# STM32_microcontroller_IOs.net
KiCad netlist of a schematic drawn in Altium Designer
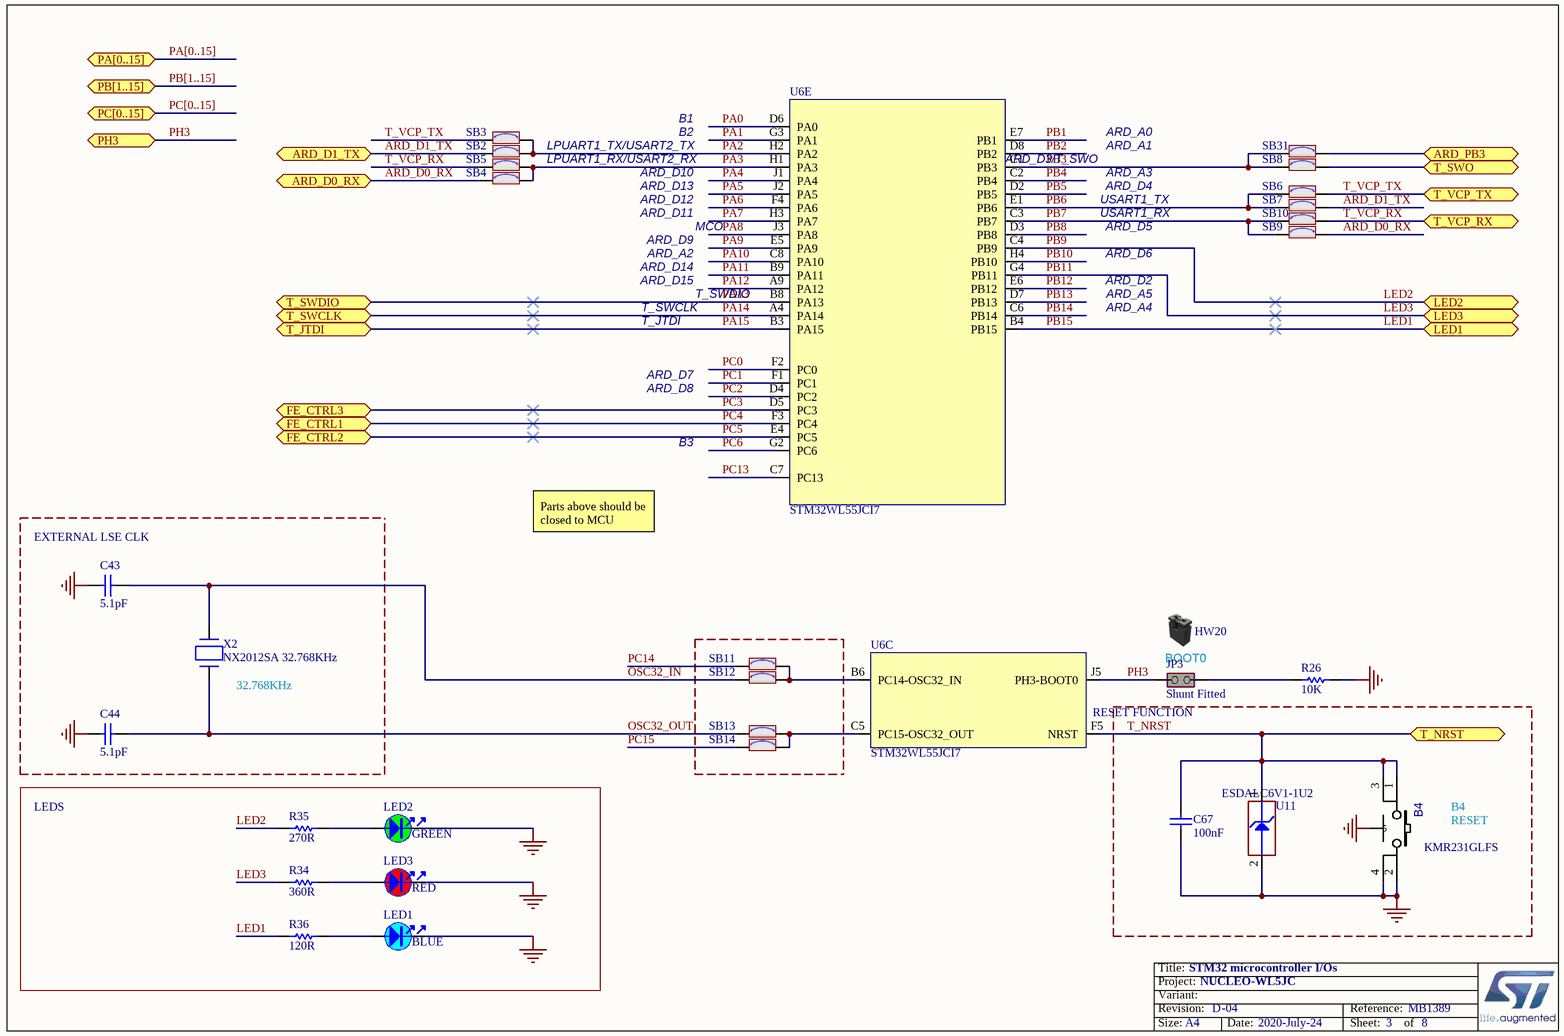
[diagram p0: STM32_microcontroller_IOs.SchDoc]

(export (version "E")
  (design (tool "Eeschema 10.0.6"))
  (components
    (comp (ref "B4")
      (value "KMR231GLFS")
      (footprint "SWI_C&K_Y78B23110FP__ITT_KMR231GLFS")
      (description "Microminiature Tact Switch for SMT - KMR 2 Series - 1.9 mm height")
      (fields
        (field (name "INTERNAL_PART_NUMBER") "MCD-01485")
        (field (name "MANUFACTURER") "C&K")
        (field (name "PROVIDED_BY") "SUBCO")
      )
      (libsource (lib "MCD_PARTS_database") (part "SW-PUSH-CMS_KMR2_BLACK"))
    )
    (comp (ref "C43")
      (value "5.1pF")
      (footprint "C0402")
      (description "Capacitor, MLCC, 5.1pF, 50V, NPO, +-0.25pF, 0402, T=0.5mm")
      (fields
        (field (name "INTERNAL_PART_NUMBER") "MCD-00003")
        (field (name "MANUFACTURER_PART_NUMBER") "CC0402CRNPO9BN5R1")
        (field (name "PROVIDED_BY") "SUBCO")
      )
      (libsource (lib "MCD_PARTS_database") (part "Capacitor"))
    )
    (comp (ref "C44")
      (value "5.1pF")
      (footprint "C0402")
      (description "Capacitor, MLCC, 5.1pF, 50V, NPO, +-0.25pF, 0402, T=0.5mm")
      (fields
        (field (name "INTERNAL_PART_NUMBER") "MCD-00003")
        (field (name "MANUFACTURER_PART_NUMBER") "CC0402CRNPO9BN5R1")
        (field (name "PROVIDED_BY") "SUBCO")
      )
      (libsource (lib "MCD_PARTS_database") (part "Capacitor"))
    )
    (comp (ref "C67")
      (value "100nF")
      (footprint "C0402")
      (description "Capacitor, MLCC, 100nF, 16V, X7R, 10%, 0402, T=0,5mm")
      (fields
        (field (name "INTERNAL_PART_NUMBER") "MCD-00102")
        (field (name "MANUFACTURER_PART_NUMBER") "CC0402KRX7R7BB104")
        (field (name "PROVIDED_BY") "SUBCO")
      )
      (libsource (lib "MCD_PARTS_database") (part "Capacitor"))
    )
    (comp (ref "HW20")
      (value "~")
      (description "SHUNT 2.54mm BLACK")
      (fields
        (field (name "INTERNAL_PART_NUMBER") "MCD-00043")
        (field (name "MANUFACTURER_PART_NUMBER") "SNT-100-BK-G")
        (field (name "PROVIDED_BY") "SUBCO")
      )
      (libsource (lib "MCD_PARTS_database") (part "Shunt Black 2.54mm"))
    )
    (comp (ref "JP3")
      (value "Shunt Fitted")
      (footprint "CON_SAMTEC_TSW-102-07-G-S")
      (description "Header, 2x1, 2,54mm, VR, TH, Height 5.84mm/2.54mm - Shunt Fitted by default")
      (fields
        (field (name "INTERNAL_PART_NUMBER") "MCD-00683")
        (field (name "MANUFACTURER_PART_NUMBER") "TSW-102-07-x-S")
        (field (name "PROVIDED_BY") "SUBCO")
      )
      (libsource (lib "MCD_PARTS_database") (part "Jumper_Header 2x1 Fitted"))
    )
    (comp (ref "LED1")
      (value "BLUE")
      (footprint "LED_0603_OSRAM_LB-Q39G-L2OO-35-1_BLUE_1A2K_H0P4")
      (description "LED Blue, 0603 SMD, Forward Voltage Min=2,8V, Max=3,8V")
      (fields
        (field (name "INTERNAL_PART_NUMBER") "MCD-00585")
        (field (name "MANUFACTURER_PART_NUMBER") "LB Q39G-L2OO-35-1")
        (field (name "PROVIDED_BY") "SUBCO")
      )
      (libsource (lib "MCD_PARTS_database") (part "LED_blue"))
    )
    (comp (ref "LED2")
      (value "GREEN")
      (footprint "LED_0603_OSRAM_LG-Q396-PS-35_GREEN_1A2K_H0P4")
      (description "LED Green, 0603 SMD, Forward Voltage Typ=2V, Max=2.5V")
      (fields
        (field (name "INTERNAL_PART_NUMBER") "MCD-00588")
        (field (name "MANUFACTURER_PART_NUMBER") "LG Q396-PS-35")
        (field (name "PROVIDED_BY") "SUBCO")
      )
      (libsource (lib "MCD_PARTS_database") (part "LED_green"))
    )
    (comp (ref "LED3")
      (value "RED")
      (footprint "LED_0603_VISHAY_VLMS1300-GS08_RED_1A2K_H0P8")
      (description "LED Red, 0603 SMD, 2V Forward Voltage")
      (fields
        (field (name "INTERNAL_PART_NUMBER") "MCD-00587")
        (field (name "MANUFACTURER_PART_NUMBER") "VLMS1300-GS08")
        (field (name "PROVIDED_BY") "SUBCO")
      )
      (libsource (lib "MCD_PARTS_database") (part "LED_red"))
    )
    (comp (ref "R26")
      (value "10K")
      (footprint "R0603")
      (description "Resistor,10K,0603,1%,1/10W")
      (fields
        (field (name "INTERNAL_PART_NUMBER") "MCD-00220")
        (field (name "MANUFACTURER_PART_NUMBER") "RC0603FR-0710KL")
        (field (name "PROVIDED_BY") "SUBCO")
      )
      (libsource (lib "MCD_PARTS_database") (part "Resistor"))
    )
    (comp (ref "R34")
      (value "360R")
      (footprint "R0402")
      (description "Resistor,360R,0402,1%,1/16W")
      (fields
        (field (name "INTERNAL_PART_NUMBER") "MCD-00461")
        (field (name "MANUFACTURER_PART_NUMBER") "RC0402FR-07360RL")
        (field (name "PROVIDED_BY") "SUBCO")
      )
      (libsource (lib "MCD_PARTS_database") (part "Resistor"))
    )
    (comp (ref "R35")
      (value "270R")
      (footprint "R0402")
      (description "Resistor,270R,0402,1%,1/16W")
      (fields
        (field (name "INTERNAL_PART_NUMBER") "MCD-00441")
        (field (name "MANUFACTURER_PART_NUMBER") "RC0402FR-07270RL")
        (field (name "PROVIDED_BY") "SUBCO")
      )
      (libsource (lib "MCD_PARTS_database") (part "Resistor"))
    )
    (comp (ref "R36")
      (value "120R")
      (footprint "R0402")
      (description "Resistor,120R,0402,1%,1/16W")
      (fields
        (field (name "INTERNAL_PART_NUMBER") "MCD-00194")
        (field (name "MANUFACTURER_PART_NUMBER") "RC0402FR-07120RL")
        (field (name "PROVIDED_BY") "SUBCO")
      )
      (libsource (lib "MCD_PARTS_database") (part "Resistor"))
    )
    (comp (ref "SB2")
      (value "~")
      (footprint "SOLDER-BRIDGE_R0603-0R")
      (description "Solder Bridge ON")
      (fields
        (field (name "INTERNAL_PART_NUMBER") "MCD-00071")
        (field (name "MANUFACTURER_PART_NUMBER") "RC0603JR-070RL")
        (field (name "PROVIDED_BY") "SUBCO")
      )
      (libsource (lib "") (part "SB_ON_1"))
    )
    (comp (ref "SB3")
      (value "~")
      (footprint "SOLDER-BRIDGE_R0603-0R")
      (description "Solder Bridge ON")
      (fields
        (field (name "INTERNAL_PART_NUMBER") "MCD-00071")
        (field (name "MANUFACTURER_PART_NUMBER") "RC0603JR-070RL")
        (field (name "PROVIDED_BY") "SUBCO")
      )
      (libsource (lib "MCD_PARTS_database") (part "SB_ON"))
    )
    (comp (ref "SB4")
      (value "~")
      (footprint "SOLDER-BRIDGE_R0603-0R")
      (description "Solder Bridge ON")
      (fields
        (field (name "INTERNAL_PART_NUMBER") "MCD-00071")
        (field (name "MANUFACTURER_PART_NUMBER") "RC0603JR-070RL")
        (field (name "PROVIDED_BY") "SUBCO")
      )
      (libsource (lib "") (part "SB_ON_1"))
    )
    (comp (ref "SB5")
      (value "~")
      (footprint "SOLDER-BRIDGE_R0603-0R")
      (description "Solder Bridge ON")
      (fields
        (field (name "INTERNAL_PART_NUMBER") "MCD-00071")
        (field (name "MANUFACTURER_PART_NUMBER") "RC0603JR-070RL")
        (field (name "PROVIDED_BY") "SUBCO")
      )
      (libsource (lib "MCD_PARTS_database") (part "SB_ON"))
    )
    (comp (ref "SB6")
      (value "~")
      (footprint "SOLDER-BRIDGE_R0603-0R")
      (description "Solder Bridge ON")
      (fields
        (field (name "INTERNAL_PART_NUMBER") "MCD-00071")
        (field (name "MANUFACTURER_PART_NUMBER") "RC0603JR-070RL")
        (field (name "PROVIDED_BY") "SUBCO")
      )
      (libsource (lib "MCD_PARTS_database") (part "SB_ON"))
    )
    (comp (ref "SB7")
      (value "~")
      (footprint "SOLDER-BRIDGE_R0603-0R")
      (description "Solder Bridge ON")
      (fields
        (field (name "INTERNAL_PART_NUMBER") "MCD-00071")
        (field (name "MANUFACTURER_PART_NUMBER") "RC0603JR-070RL")
        (field (name "PROVIDED_BY") "SUBCO")
      )
      (libsource (lib "") (part "SB_ON_1"))
    )
    (comp (ref "SB8")
      (value "~")
      (footprint "SOLDER-BRIDGE_R0603-0R")
      (description "Solder Bridge ON")
      (fields
        (field (name "INTERNAL_PART_NUMBER") "MCD-00071")
        (field (name "MANUFACTURER_PART_NUMBER") "RC0603JR-070RL")
        (field (name "PROVIDED_BY") "SUBCO")
      )
      (libsource (lib "MCD_PARTS_database") (part "SB_ON"))
    )
    (comp (ref "SB9")
      (value "~")
      (footprint "SOLDER-BRIDGE_R0603-0R")
      (description "Solder Bridge ON")
      (fields
        (field (name "INTERNAL_PART_NUMBER") "MCD-00071")
        (field (name "MANUFACTURER_PART_NUMBER") "RC0603JR-070RL")
        (field (name "PROVIDED_BY") "SUBCO")
      )
      (libsource (lib "") (part "SB_ON_1"))
    )
    (comp (ref "SB10")
      (value "~")
      (footprint "SOLDER-BRIDGE_R0603-0R")
      (description "Solder Bridge ON")
      (fields
        (field (name "INTERNAL_PART_NUMBER") "MCD-00071")
        (field (name "MANUFACTURER_PART_NUMBER") "RC0603JR-070RL")
        (field (name "PROVIDED_BY") "SUBCO")
      )
      (libsource (lib "MCD_PARTS_database") (part "SB_ON"))
    )
    (comp (ref "SB11")
      (value "~")
      (footprint "SOLDER-BRIDGE_R0603-0R")
      (description "Solder Bridge ON")
      (fields
        (field (name "INTERNAL_PART_NUMBER") "MCD-00071")
        (field (name "MANUFACTURER_PART_NUMBER") "RC0603JR-070RL")
        (field (name "PROVIDED_BY") "SUBCO")
      )
      (libsource (lib "MCD_PARTS_database") (part "SB_ON"))
    )
    (comp (ref "SB12")
      (value "~")
      (footprint "SOLDER-BRIDGE_R0603-0R")
      (description "Solder Bridge ON")
      (fields
        (field (name "INTERNAL_PART_NUMBER") "MCD-00071")
        (field (name "MANUFACTURER_PART_NUMBER") "RC0603JR-070RL")
        (field (name "PROVIDED_BY") "SUBCO")
      )
      (libsource (lib "MCD_PARTS_database") (part "SB_ON"))
    )
    (comp (ref "SB13")
      (value "~")
      (footprint "SOLDER-BRIDGE_R0603-0R")
      (description "Solder Bridge ON")
      (fields
        (field (name "INTERNAL_PART_NUMBER") "MCD-00071")
        (field (name "MANUFACTURER_PART_NUMBER") "RC0603JR-070RL")
        (field (name "PROVIDED_BY") "SUBCO")
      )
      (libsource (lib "MCD_PARTS_database") (part "SB_ON"))
    )
    (comp (ref "SB14")
      (value "~")
      (footprint "SOLDER-BRIDGE_R0603-0R")
      (description "Solder Bridge ON")
      (fields
        (field (name "INTERNAL_PART_NUMBER") "MCD-00071")
        (field (name "MANUFACTURER_PART_NUMBER") "RC0603JR-070RL")
        (field (name "PROVIDED_BY") "SUBCO")
      )
      (libsource (lib "MCD_PARTS_database") (part "SB_ON"))
    )
    (comp (ref "SB31")
      (value "~")
      (footprint "SOLDER-BRIDGE_R0603-0R")
      (description "Solder Bridge ON")
      (fields
        (field (name "INTERNAL_PART_NUMBER") "MCD-00071")
        (field (name "MANUFACTURER_PART_NUMBER") "RC0603JR-070RL")
        (field (name "PROVIDED_BY") "SUBCO")
      )
      (libsource (lib "MCD_PARTS_database") (part "SB_ON"))
    )
    (comp (ref "U6")
      (value "STM32WL55JCI7")
      (footprint "ICC_UFBGA73_5X5_P050")
      (description "Multiprotocol Wireless 32-bit MCUwith LPWAN Sub-GHz radio solution")
      (fields
        (field (name "INTERNAL_PART_NUMBER") "MCD-01435")
        (field (name "MANUFACTURER") "STMICROELECTRONICS")
      )
      (libsource (lib "MCD_PARTS_database") (part "STM32WL5x_BGA73"))
    )
    (comp (ref "U11")
      (value "ESDALC6V1-1U2")
      (footprint "ESD_ST0201")
      (description "ESD protection 6V1")
      (fields
        (field (name "INTERNAL_PART_NUMBER") "MCD-00170")
        (field (name "MANUFACTURER") "STMICROELECTRONICS")
        (field (name "PROVIDED_BY") "SUBCO with ST control")
      )
      (libsource (lib "MCD_PARTS_database") (part "ESD-TRANSIL"))
    )
    (comp (ref "X2")
      (value "NX2012SA 32.768KHz")
      (footprint "CRY_NX2012SA_2P")
      (description "Crystal 32.768kHz, 6pF, -+20ppm, 80Kohm max, SMD")
      (fields
        (field (name "INTERNAL_PART_NUMBER") "MCD-01479")
        (field (name "MANUFACTURER_PART_NUMBER") "NX2012SA 32.768KHz EXS00A-MU00527")
        (field (name "PROVIDED_BY") "SUBCO")
      )
      (libsource (lib "MCD_PARTS_database") (part "XTAL_2_PINS"))
    )
  )
  (nets
    (net (code "7") (name "/ARD_D0_RX") (class "Default")
      (node (ref "SB4") (pin "2") (pinfunction "2_2") (pintype "passive"))
      (node (ref "SB9") (pin "1") (pinfunction "1_1") (pintype "passive"))
    )
    (net (code "8") (name "/ARD_D1_TX") (class "Default")
      (node (ref "SB2") (pin "2") (pinfunction "2_2") (pintype "passive"))
      (node (ref "SB7") (pin "1") (pinfunction "1_1") (pintype "passive"))
    )
    (net (code "9") (name "/ARD_PB3") (class "Default")
      (node (ref "SB31") (pin "2") (pinfunction "2_2") (pintype "passive"))
    )
    (net (code "10") (name "/OSC32_IN") (class "Default")
      (node (ref "C43") (pin "1") (pinfunction "1_1") (pintype "passive"))
      (node (ref "SB12") (pin "1") (pinfunction "1_1") (pintype "passive"))
      (node (ref "X2") (pin "2") (pinfunction "X2_2") (pintype "passive"))
    )
    (net (code "11") (name "/OSC32_OUT") (class "Default")
      (node (ref "C44") (pin "1") (pinfunction "1_1") (pintype "passive"))
      (node (ref "SB13") (pin "1") (pinfunction "1_1") (pintype "passive"))
      (node (ref "X2") (pin "1") (pinfunction "X1_1") (pintype "passive"))
    )
    (net (code "12") (name "/PA0") (class "Default")
      (node (ref "U6") (pin "D6") (pinfunction "PA0_D6") (pintype "passive"))
    )
    (net (code "13") (name "/PA1") (class "Default")
      (node (ref "U6") (pin "G3") (pinfunction "PA1_G3") (pintype "passive"))
    )
    (net (code "14") (name "/PA2") (class "Default")
      (node (ref "SB2") (pin "1") (pinfunction "1_1") (pintype "passive"))
      (node (ref "SB3") (pin "2") (pinfunction "2_2") (pintype "passive"))
      (node (ref "U6") (pin "H2") (pinfunction "PA2_H2") (pintype "passive"))
    )
    (net (code "15") (name "/PA3") (class "Default")
      (node (ref "SB4") (pin "1") (pinfunction "1_1") (pintype "passive"))
      (node (ref "SB5") (pin "2") (pinfunction "2_2") (pintype "passive"))
      (node (ref "U6") (pin "H1") (pinfunction "PA3_H1") (pintype "passive"))
    )
    (net (code "16") (name "/PA4") (class "Default")
      (node (ref "U6") (pin "J1") (pinfunction "PA4_J1") (pintype "passive"))
    )
    (net (code "17") (name "/PA5") (class "Default")
      (node (ref "U6") (pin "J2") (pinfunction "PA5_J2") (pintype "passive"))
    )
    (net (code "18") (name "/PA6") (class "Default")
      (node (ref "U6") (pin "F4") (pinfunction "PA6_F4") (pintype "passive"))
    )
    (net (code "19") (name "/PA7") (class "Default")
      (node (ref "U6") (pin "H3") (pinfunction "PA7_H3") (pintype "passive"))
    )
    (net (code "20") (name "/PA8") (class "Default")
      (node (ref "U6") (pin "J3") (pinfunction "PA8_J3") (pintype "passive"))
    )
    (net (code "21") (name "/PA9") (class "Default")
      (node (ref "U6") (pin "E5") (pinfunction "PA9_E5") (pintype "passive"))
    )
    (net (code "22") (name "/PA10") (class "Default")
      (node (ref "U6") (pin "C8") (pinfunction "PA10_C8") (pintype "passive"))
    )
    (net (code "23") (name "/PA11") (class "Default")
      (node (ref "U6") (pin "B9") (pinfunction "PA11_B9") (pintype "passive"))
    )
    (net (code "24") (name "/PA12") (class "Default")
      (node (ref "U6") (pin "A9") (pinfunction "PA12_A9") (pintype "passive"))
    )
    (net (code "25") (name "/PA13") (class "Default")
      (node (ref "U6") (pin "B8") (pinfunction "PA13_B8") (pintype "passive"))
    )
    (net (code "26") (name "/PA14") (class "Default")
      (node (ref "U6") (pin "A4") (pinfunction "PA14_A4") (pintype "passive"))
    )
    (net (code "27") (name "/PA15") (class "Default")
      (node (ref "U6") (pin "B3") (pinfunction "PA15_B3") (pintype "passive"))
    )
    (net (code "29") (name "/PB1") (class "Default")
      (node (ref "U6") (pin "E7") (pinfunction "PB1_E7") (pintype "passive"))
    )
    (net (code "30") (name "/PB2") (class "Default")
      (node (ref "U6") (pin "D8") (pinfunction "PB2_D8") (pintype "passive"))
    )
    (net (code "31") (name "/PB3") (class "Default")
      (node (ref "SB31") (pin "1") (pinfunction "1_1") (pintype "passive"))
      (node (ref "SB8") (pin "1") (pinfunction "1_1") (pintype "passive"))
      (node (ref "U6") (pin "C1") (pinfunction "PB3_C1") (pintype "passive"))
    )
    (net (code "32") (name "/PB4") (class "Default")
      (node (ref "U6") (pin "C2") (pinfunction "PB4_C2") (pintype "passive"))
    )
    (net (code "33") (name "/PB5") (class "Default")
      (node (ref "U6") (pin "D2") (pinfunction "PB5_D2") (pintype "passive"))
    )
    (net (code "34") (name "/PB6") (class "Default")
      (node (ref "SB6") (pin "1") (pinfunction "1_1") (pintype "passive"))
      (node (ref "SB7") (pin "2") (pinfunction "2_2") (pintype "passive"))
      (node (ref "U6") (pin "E1") (pinfunction "PB6_E1") (pintype "passive"))
    )
    (net (code "35") (name "/PB7") (class "Default")
      (node (ref "SB10") (pin "1") (pinfunction "1_1") (pintype "passive"))
      (node (ref "SB9") (pin "2") (pinfunction "2_2") (pintype "passive"))
      (node (ref "U6") (pin "C3") (pinfunction "PB7_C3") (pintype "passive"))
    )
    (net (code "36") (name "/PB8") (class "Default")
      (node (ref "U6") (pin "D3") (pinfunction "PB8_D3") (pintype "passive"))
    )
    (net (code "37") (name "/PB9") (class "Default")
      (node (ref "R35") (pin "1") (pinfunction "1_1") (pintype "passive"))
      (node (ref "U6") (pin "C4") (pinfunction "PB9_C4") (pintype "passive"))
    )
    (net (code "38") (name "/PB10") (class "Default")
      (node (ref "U6") (pin "H4") (pinfunction "PB10_H4") (pintype "passive"))
    )
    (net (code "39") (name "/PB11") (class "Default")
      (node (ref "R34") (pin "1") (pinfunction "1_1") (pintype "passive"))
      (node (ref "U6") (pin "G4") (pinfunction "PB11_G4") (pintype "passive"))
    )
    (net (code "40") (name "/PB12") (class "Default")
      (node (ref "U6") (pin "E6") (pinfunction "PB12_E6") (pintype "passive"))
    )
    (net (code "41") (name "/PB13") (class "Default")
      (node (ref "U6") (pin "D7") (pinfunction "PB13_D7") (pintype "passive"))
    )
    (net (code "42") (name "/PB14") (class "Default")
      (node (ref "U6") (pin "C6") (pinfunction "PB14_C6") (pintype "passive"))
    )
    (net (code "43") (name "/PB15") (class "Default")
      (node (ref "R36") (pin "1") (pinfunction "1_1") (pintype "passive"))
      (node (ref "U6") (pin "B4") (pinfunction "PB15_B4") (pintype "passive"))
    )
    (net (code "45") (name "/PC0") (class "Default")
      (node (ref "U6") (pin "F2") (pinfunction "PC0_F2") (pintype "passive"))
    )
    (net (code "46") (name "/PC1") (class "Default")
      (node (ref "U6") (pin "F1") (pinfunction "PC1_F1") (pintype "passive"))
    )
    (net (code "47") (name "/PC2") (class "Default")
      (node (ref "U6") (pin "D4") (pinfunction "PC2_D4") (pintype "passive"))
    )
    (net (code "48") (name "/PC3") (class "Default")
      (node (ref "U6") (pin "D5") (pinfunction "PC3_D5") (pintype "passive"))
    )
    (net (code "49") (name "/PC4") (class "Default")
      (node (ref "U6") (pin "F3") (pinfunction "PC4_F3") (pintype "passive"))
    )
    (net (code "50") (name "/PC5") (class "Default")
      (node (ref "U6") (pin "E4") (pinfunction "PC5_E4") (pintype "passive"))
    )
    (net (code "51") (name "/PC6") (class "Default")
      (node (ref "U6") (pin "G2") (pinfunction "PC6_G2") (pintype "passive"))
    )
    (net (code "52") (name "/PC13") (class "Default")
      (node (ref "U6") (pin "C7") (pinfunction "PC13_C7") (pintype "passive"))
    )
    (net (code "53") (name "/PC14") (class "Default")
      (node (ref "SB11") (pin "1") (pinfunction "1_1") (pintype "passive"))
    )
    (net (code "54") (name "/PC15") (class "Default")
      (node (ref "SB14") (pin "1") (pinfunction "1_1") (pintype "passive"))
    )
    (net (code "56") (name "/PH3") (class "Default")
      (node (ref "JP3") (pin "1") (pinfunction "COMMON_1") (pintype "passive"))
      (node (ref "U6") (pin "J5") (pinfunction "PH3-BOOT0_J5") (pintype "passive"))
    )
    (net (code "57") (name "/T_NRST") (class "Default")
      (node (ref "B4") (pin "1") (pinfunction "1_1") (pintype "passive"))
      (node (ref "B4") (pin "3") (pinfunction "3_3") (pintype "passive"))
      (node (ref "C67") (pin "2") (pinfunction "2_2") (pintype "passive"))
      (node (ref "U11") (pin "1") (pinfunction "IO1_1") (pintype "passive"))
      (node (ref "U6") (pin "F5") (pinfunction "NRST_F5") (pintype "passive"))
    )
    (net (code "58") (name "/T_SWO") (class "Default")
      (node (ref "SB8") (pin "2") (pinfunction "2_2") (pintype "passive"))
    )
    (net (code "59") (name "/T_VCP_RX") (class "Default")
      (node (ref "SB10") (pin "2") (pinfunction "2_2") (pintype "passive"))
      (node (ref "SB5") (pin "1") (pinfunction "1_1") (pintype "passive"))
    )
    (net (code "60") (name "/T_VCP_TX") (class "Default")
      (node (ref "SB3") (pin "1") (pinfunction "1_1") (pintype "passive"))
      (node (ref "SB6") (pin "2") (pinfunction "2_2") (pintype "passive"))
    )
    (net (code "61") (name "GND") (class "Default")
      (node (ref "B4") (pin "2") (pinfunction "2_2") (pintype "passive"))
      (node (ref "B4") (pin "4") (pinfunction "4_4") (pintype "passive"))
      (node (ref "B4") (pin "5") (pinfunction "5_5") (pintype "passive"))
      (node (ref "C43") (pin "2") (pinfunction "2_2") (pintype "passive"))
      (node (ref "C44") (pin "2") (pinfunction "2_2") (pintype "passive"))
      (node (ref "C67") (pin "1") (pinfunction "1_1") (pintype "passive"))
      (node (ref "LED1") (pin "2") (pintype "passive"))
      (node (ref "LED2") (pin "2") (pintype "passive"))
      (node (ref "LED3") (pin "2") (pintype "passive"))
      (node (ref "R26") (pin "1") (pinfunction "1_1") (pintype "passive"))
      (node (ref "U11") (pin "2") (pinfunction "GND_2") (pintype "passive"))
    )
    (net (code "62") (name "Net-(JP3-NO)") (class "Default")
      (node (ref "JP3") (pin "2") (pinfunction "NO_2") (pintype "passive"))
      (node (ref "R26") (pin "2") (pinfunction "2_2") (pintype "passive"))
    )
    (net (code "63") (name "Net-(LED1-Pad1)") (class "Default")
      (node (ref "LED1") (pin "1") (pintype "passive"))
      (node (ref "R36") (pin "2") (pinfunction "2_2") (pintype "passive"))
    )
    (net (code "64") (name "Net-(LED2-Pad1)") (class "Default")
      (node (ref "LED2") (pin "1") (pintype "passive"))
      (node (ref "R35") (pin "2") (pinfunction "2_2") (pintype "passive"))
    )
    (net (code "65") (name "Net-(LED3-Pad1)") (class "Default")
      (node (ref "LED3") (pin "1") (pintype "passive"))
      (node (ref "R34") (pin "2") (pinfunction "2_2") (pintype "passive"))
    )
    (net (code "66") (name "Net-(U6C-PC14-OSC32_IN)") (class "Default")
      (node (ref "SB11") (pin "2") (pinfunction "2_2") (pintype "passive"))
      (node (ref "SB12") (pin "2") (pinfunction "2_2") (pintype "passive"))
      (node (ref "U6") (pin "B6") (pinfunction "PC14-OSC32_IN_B6") (pintype "passive"))
    )
    (net (code "67") (name "Net-(U6C-PC15-OSC32_OUT)") (class "Default")
      (node (ref "SB13") (pin "2") (pinfunction "2_2") (pintype "passive"))
      (node (ref "SB14") (pin "2") (pinfunction "2_2") (pintype "passive"))
      (node (ref "U6") (pin "C5") (pinfunction "PC15-OSC32_OUT_C5") (pintype "passive"))
    )
  )
)
